# SCH-mfd-menu-panel.net
KiCad netlist of a schematic drawn in EasyEDA
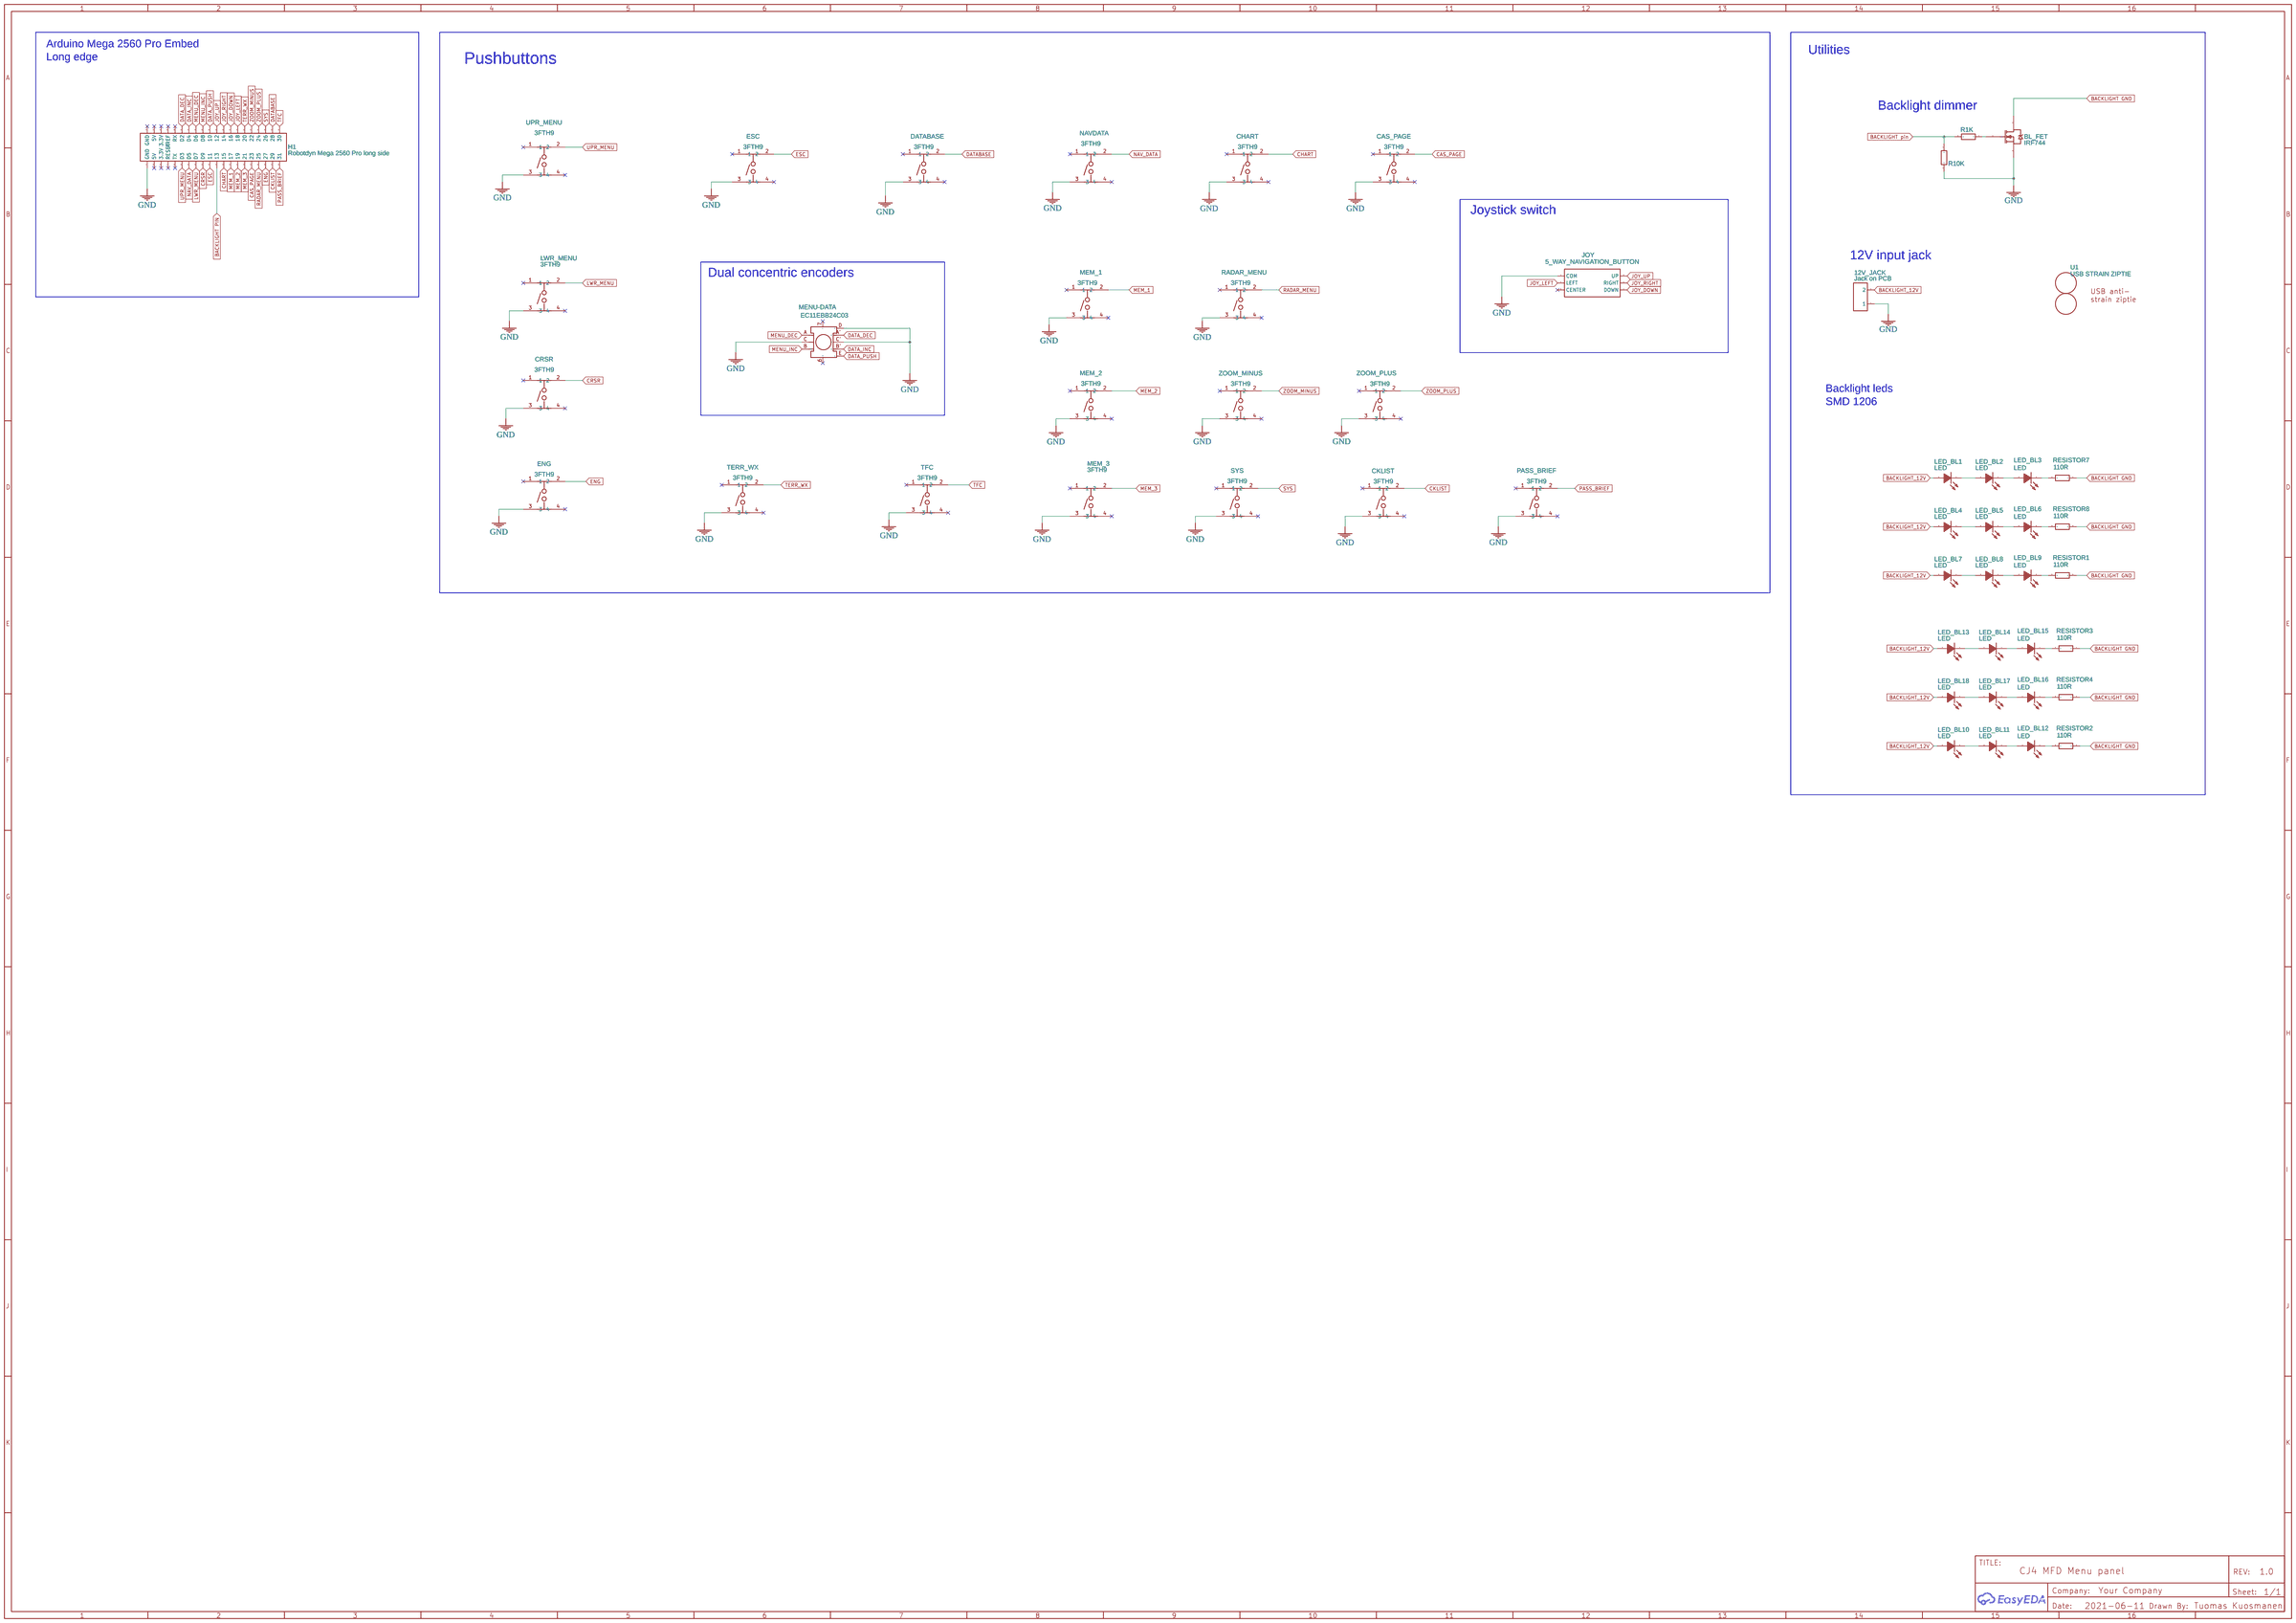
[diagram p0: schematic sheet]

(export (version "E")
  (design (tool "Eeschema 10.0.6"))
  (components
    (comp (ref "12V_JACK") (value "Jack on PCB") (libsource (lib "") (part "J-Header-Male-2.54_1x2")))
    (comp (ref "BL_FET") (value "IRF744") (libsource (lib "") (part "IRF744")))
    (comp (ref "CAS_PAGE")
      (value "3FTH9")
      (fields (field (name "BOM_Supplier Part") "679-3730-5-ND"))
      (libsource (lib "") (part "3FTH9_13"))
    )
    (comp (ref "CHART")
      (value "3FTH9")
      (fields (field (name "BOM_Supplier Part") "679-3730-5-ND"))
      (libsource (lib "") (part "3FTH9_6"))
    )
    (comp (ref "CKLIST")
      (value "3FTH9")
      (fields (field (name "BOM_Supplier Part") "679-3730-5-ND"))
      (libsource (lib "") (part "3FTH9_7"))
    )
    (comp (ref "CRSR")
      (value "3FTH9")
      (fields (field (name "BOM_Supplier Part") "679-3730-5-ND"))
      (libsource (lib "") (part "3FTH9_12"))
    )
    (comp (ref "DATABASE")
      (value "3FTH9")
      (fields (field (name "BOM_Supplier Part") "679-3730-5-ND"))
      (libsource (lib "") (part "3FTH9_4"))
    )
    (comp (ref "ENG")
      (value "3FTH9")
      (fields (field (name "BOM_Supplier Part") "679-3730-5-ND"))
      (libsource (lib "") (part "3FTH9_2"))
    )
    (comp (ref "ESC")
      (value "3FTH9")
      (fields (field (name "BOM_Supplier Part") "679-3730-5-ND"))
      (libsource (lib "") (part "3FTH9_16"))
    )
    (comp (ref "H1")
      (value "Robotdyn Mega 2560 Pro long side")
      (fields
        (field (name "BOM_Manufacturer Part") "Header-Male-2.54_2x20")
        (field (name "BOM_Supplier Part") "C50980")
      )
      (libsource (lib "") (part "Header-Male-2.54_2x20"))
    )
    (comp (ref "JOY")
      (value "5_WAY_NAVIGATION_BUTTON")
      (fields (field (name "BOM_Manufacturer Part") "New SchematicLib"))
      (libsource (lib "") (part "5_WAY_NAVIGATION_BUTTON"))
    )
    (comp (ref "LED_BL1")
      (value "LED")
      (fields
        (field (name "BOM_Manufacturer Part") "HQ17-2102UYOC")
        (field (name "BOM_Supplier Part") "C154481")
      )
      (libsource (lib "") (part "HQ17-2102UYOC"))
    )
    (comp (ref "LED_BL2")
      (value "LED")
      (fields
        (field (name "BOM_Manufacturer Part") "HQ17-2102UYOC")
        (field (name "BOM_Supplier Part") "C154481")
      )
      (libsource (lib "") (part "HQ17-2102UYOC"))
    )
    (comp (ref "LED_BL3")
      (value "LED")
      (fields
        (field (name "BOM_Manufacturer Part") "HQ17-2102UYOC")
        (field (name "BOM_Supplier Part") "C154481")
      )
      (libsource (lib "") (part "HQ17-2102UYOC"))
    )
    (comp (ref "LED_BL4")
      (value "LED")
      (fields
        (field (name "BOM_Manufacturer Part") "HQ17-2102UYOC")
        (field (name "BOM_Supplier Part") "C154481")
      )
      (libsource (lib "") (part "HQ17-2102UYOC"))
    )
    (comp (ref "LED_BL5")
      (value "LED")
      (fields
        (field (name "BOM_Manufacturer Part") "HQ17-2102UYOC")
        (field (name "BOM_Supplier Part") "C154481")
      )
      (libsource (lib "") (part "HQ17-2102UYOC"))
    )
    (comp (ref "LED_BL6")
      (value "LED")
      (fields
        (field (name "BOM_Manufacturer Part") "HQ17-2102UYOC")
        (field (name "BOM_Supplier Part") "C154481")
      )
      (libsource (lib "") (part "HQ17-2102UYOC"))
    )
    (comp (ref "LED_BL7")
      (value "LED")
      (fields
        (field (name "BOM_Manufacturer Part") "HQ17-2102UYOC")
        (field (name "BOM_Supplier Part") "C154481")
      )
      (libsource (lib "") (part "HQ17-2102UYOC"))
    )
    (comp (ref "LED_BL8")
      (value "LED")
      (fields
        (field (name "BOM_Manufacturer Part") "HQ17-2102UYOC")
        (field (name "BOM_Supplier Part") "C154481")
      )
      (libsource (lib "") (part "HQ17-2102UYOC"))
    )
    (comp (ref "LED_BL9")
      (value "LED")
      (fields
        (field (name "BOM_Manufacturer Part") "HQ17-2102UYOC")
        (field (name "BOM_Supplier Part") "C154481")
      )
      (libsource (lib "") (part "HQ17-2102UYOC"))
    )
    (comp (ref "LED_BL10")
      (value "LED")
      (fields
        (field (name "BOM_Manufacturer Part") "HQ17-2102UYOC")
        (field (name "BOM_Supplier Part") "C154481")
      )
      (libsource (lib "") (part "HQ17-2102UYOC"))
    )
    (comp (ref "LED_BL11")
      (value "LED")
      (fields
        (field (name "BOM_Manufacturer Part") "HQ17-2102UYOC")
        (field (name "BOM_Supplier Part") "C154481")
      )
      (libsource (lib "") (part "HQ17-2102UYOC"))
    )
    (comp (ref "LED_BL12")
      (value "LED")
      (fields
        (field (name "BOM_Manufacturer Part") "HQ17-2102UYOC")
        (field (name "BOM_Supplier Part") "C154481")
      )
      (libsource (lib "") (part "HQ17-2102UYOC"))
    )
    (comp (ref "LED_BL13")
      (value "LED")
      (fields
        (field (name "BOM_Manufacturer Part") "HQ17-2102UYOC")
        (field (name "BOM_Supplier Part") "C154481")
      )
      (libsource (lib "") (part "HQ17-2102UYOC"))
    )
    (comp (ref "LED_BL14")
      (value "LED")
      (fields
        (field (name "BOM_Manufacturer Part") "HQ17-2102UYOC")
        (field (name "BOM_Supplier Part") "C154481")
      )
      (libsource (lib "") (part "HQ17-2102UYOC"))
    )
    (comp (ref "LED_BL15")
      (value "LED")
      (fields
        (field (name "BOM_Manufacturer Part") "HQ17-2102UYOC")
        (field (name "BOM_Supplier Part") "C154481")
      )
      (libsource (lib "") (part "HQ17-2102UYOC"))
    )
    (comp (ref "LED_BL16")
      (value "LED")
      (fields
        (field (name "BOM_Manufacturer Part") "HQ17-2102UYOC")
        (field (name "BOM_Supplier Part") "C154481")
      )
      (libsource (lib "") (part "HQ17-2102UYOC"))
    )
    (comp (ref "LED_BL17")
      (value "LED")
      (fields
        (field (name "BOM_Manufacturer Part") "HQ17-2102UYOC")
        (field (name "BOM_Supplier Part") "C154481")
      )
      (libsource (lib "") (part "HQ17-2102UYOC"))
    )
    (comp (ref "LED_BL18")
      (value "LED")
      (fields
        (field (name "BOM_Manufacturer Part") "HQ17-2102UYOC")
        (field (name "BOM_Supplier Part") "C154481")
      )
      (libsource (lib "") (part "HQ17-2102UYOC"))
    )
    (comp (ref "LWR_MENU")
      (value "3FTH9")
      (fields (field (name "BOM_Supplier Part") "679-3730-5-ND"))
      (libsource (lib "") (part "3FTH9_1"))
    )
    (comp (ref "MEM_1")
      (value "3FTH9")
      (fields (field (name "BOM_Supplier Part") "679-3730-5-ND"))
      (libsource (lib "") (part "3FTH9"))
    )
    (comp (ref "MEM_2")
      (value "3FTH9")
      (fields (field (name "BOM_Supplier Part") "679-3730-5-ND"))
      (libsource (lib "") (part "3FTH9"))
    )
    (comp (ref "MEM_3")
      (value "3FTH9")
      (fields (field (name "BOM_Supplier Part") "679-3730-5-ND"))
      (libsource (lib "") (part "3FTH9"))
    )
    (comp (ref "MENU-DATA")
      (value "EC11EBB24C03")
      (fields (field (name "BOM_Supplier Part") "C470790"))
      (libsource (lib "") (part "EC11EBB24C03"))
    )
    (comp (ref "NAVDATA")
      (value "3FTH9")
      (fields (field (name "BOM_Supplier Part") "679-3730-5-ND"))
      (libsource (lib "") (part "3FTH9_15"))
    )
    (comp (ref "PASS_BRIEF")
      (value "3FTH9")
      (fields (field (name "BOM_Supplier Part") "679-3730-5-ND"))
      (libsource (lib "") (part "3FTH9_5"))
    )
    (comp (ref "PROTECT_BL1")
      (value "R1K")
      (fields
        (field (name "BOM_Manufacturer Part") "1206W4J0331T5E")
        (field (name "BOM_Supplier Part") "C25374")
      )
      (libsource (lib "") (part "1206W4J0331T5E_1"))
    )
    (comp (ref "RADAR_MENU")
      (value "3FTH9")
      (fields (field (name "BOM_Supplier Part") "679-3730-5-ND"))
      (libsource (lib "") (part "3FTH9_3"))
    )
    (comp (ref "RESISTOR1")
      (value "110R")
      (fields
        (field (name "BOM_Manufacturer Part") "1206W4J0331T5E")
        (field (name "BOM_Supplier Part") "C25374")
      )
      (libsource (lib "") (part "1206W4J0331T5E"))
    )
    (comp (ref "RESISTOR2")
      (value "110R")
      (fields
        (field (name "BOM_Manufacturer Part") "1206W4J0331T5E")
        (field (name "BOM_Supplier Part") "C25374")
      )
      (libsource (lib "") (part "1206W4J0331T5E"))
    )
    (comp (ref "RESISTOR3")
      (value "110R")
      (fields
        (field (name "BOM_Manufacturer Part") "1206W4J0331T5E")
        (field (name "BOM_Supplier Part") "C25374")
      )
      (libsource (lib "") (part "1206W4J0331T5E"))
    )
    (comp (ref "RESISTOR4")
      (value "110R")
      (fields
        (field (name "BOM_Manufacturer Part") "1206W4J0331T5E")
        (field (name "BOM_Supplier Part") "C25374")
      )
      (libsource (lib "") (part "1206W4J0331T5E"))
    )
    (comp (ref "RESISTOR7")
      (value "110R")
      (fields
        (field (name "BOM_Manufacturer Part") "1206W4J0331T5E")
        (field (name "BOM_Supplier Part") "C25374")
      )
      (libsource (lib "") (part "1206W4J0331T5E"))
    )
    (comp (ref "RESISTOR8")
      (value "110R")
      (fields
        (field (name "BOM_Manufacturer Part") "1206W4J0331T5E")
        (field (name "BOM_Supplier Part") "C25374")
      )
      (libsource (lib "") (part "1206W4J0331T5E"))
    )
    (comp (ref "R_ANN5")
      (value "R10K")
      (fields
        (field (name "BOM_Manufacturer Part") "1206W4J0331T5E")
        (field (name "BOM_Supplier Part") "C25374")
      )
      (libsource (lib "") (part "1206W4J0331T5E_2"))
    )
    (comp (ref "SYS")
      (value "3FTH9")
      (fields (field (name "BOM_Supplier Part") "679-3730-5-ND"))
      (libsource (lib "") (part "3FTH9_14"))
    )
    (comp (ref "TERR_WX")
      (value "3FTH9")
      (fields (field (name "BOM_Supplier Part") "679-3730-5-ND"))
      (libsource (lib "") (part "3FTH9_17"))
    )
    (comp (ref "TFC")
      (value "3FTH9")
      (fields (field (name "BOM_Supplier Part") "679-3730-5-ND"))
      (libsource (lib "") (part "3FTH9_8"))
    )
    (comp (ref "U1") (value "USB STRAIN ZIPTIE") (libsource (lib "") (part "USB STRAIN ZIPTIE")))
    (comp (ref "UPR_MENU")
      (value "3FTH9")
      (fields (field (name "BOM_Supplier Part") "679-3730-5-ND"))
      (libsource (lib "") (part "3FTH9_11"))
    )
    (comp (ref "ZOOM_MINUS")
      (value "3FTH9")
      (fields (field (name "BOM_Supplier Part") "679-3730-5-ND"))
      (libsource (lib "") (part "3FTH9_10"))
    )
    (comp (ref "ZOOM_PLUS")
      (value "3FTH9")
      (fields (field (name "BOM_Supplier Part") "679-3730-5-ND"))
      (libsource (lib "") (part "3FTH9_9"))
    )
  )
  (nets
    (net (code "1") (name "BACKLIGHT GND") (class "Default")
      (node (ref "BL_FET") (pin "2") (pinfunction "D_2") (pintype "unspecified"))
      (node (ref "RESISTOR1") (pin "1") (pinfunction "1_1") (pintype "input"))
      (node (ref "RESISTOR2") (pin "1") (pinfunction "1_1") (pintype "input"))
      (node (ref "RESISTOR3") (pin "1") (pinfunction "1_1") (pintype "input"))
      (node (ref "RESISTOR4") (pin "1") (pinfunction "1_1") (pintype "input"))
      (node (ref "RESISTOR7") (pin "1") (pinfunction "1_1") (pintype "input"))
      (node (ref "RESISTOR8") (pin "1") (pinfunction "1_1") (pintype "input"))
    )
    (net (code "2") (name "BACKLIGHT PIN") (class "Default")
      (node (ref "H1") (pin "21") (pinfunction "13_21") (pintype "input"))
    )
    (net (code "3") (name "BACKLIGHT pin") (class "Default")
      (node (ref "PROTECT_BL1") (pin "2") (pinfunction "2_2") (pintype "input"))
      (node (ref "R_ANN5") (pin "1") (pinfunction "1_1") (pintype "input"))
    )
    (net (code "4") (name "BACKLIGHT_12V") (class "Default")
      (node (ref "12V_JACK") (pin "2") (pinfunction "2_2") (pintype "unspecified"))
      (node (ref "LED_BL1") (pin "2") (pinfunction "A_2") (pintype "unspecified"))
      (node (ref "LED_BL10") (pin "2") (pinfunction "A_2") (pintype "unspecified"))
      (node (ref "LED_BL13") (pin "2") (pinfunction "A_2") (pintype "unspecified"))
      (node (ref "LED_BL18") (pin "2") (pinfunction "A_2") (pintype "unspecified"))
      (node (ref "LED_BL4") (pin "2") (pinfunction "A_2") (pintype "unspecified"))
      (node (ref "LED_BL7") (pin "2") (pinfunction "A_2") (pintype "unspecified"))
    )
    (net (code "5") (name "CAS_PAGE") (class "Default")
      (node (ref "CAS_PAGE") (pin "2") (pinfunction "2_2") (pintype "unspecified"))
      (node (ref "H1") (pin "31") (pinfunction "23_31") (pintype "input"))
    )
    (net (code "6") (name "CHART") (class "Default")
      (node (ref "CHART") (pin "2") (pinfunction "2_2") (pintype "unspecified"))
      (node (ref "H1") (pin "23") (pinfunction "15_23") (pintype "input"))
    )
    (net (code "7") (name "CKLIST") (class "Default")
      (node (ref "CKLIST") (pin "2") (pinfunction "2_2") (pintype "unspecified"))
      (node (ref "H1") (pin "37") (pinfunction "29_37") (pintype "input"))
    )
    (net (code "8") (name "CRSR") (class "Default")
      (node (ref "CRSR") (pin "2") (pinfunction "2_2") (pintype "unspecified"))
      (node (ref "H1") (pin "17") (pinfunction "D9_17") (pintype "input"))
    )
    (net (code "9") (name "DATABASE") (class "Default")
      (node (ref "DATABASE") (pin "2") (pinfunction "2_2") (pintype "unspecified"))
      (node (ref "H1") (pin "38") (pinfunction "28_38") (pintype "input"))
    )
    (net (code "10") (name "DATA_DEC") (class "Default")
      (node (ref "H1") (pin "12") (pinfunction "D2_12") (pintype "input"))
      (node (ref "MENU-DATA") (pin "A'") (pinfunction "A'_A'") (pintype "unspecified"))
    )
    (net (code "11") (name "DATA_INC") (class "Default")
      (node (ref "H1") (pin "14") (pinfunction "D4_14") (pintype "input"))
      (node (ref "MENU-DATA") (pin "B'") (pinfunction "B'_B'") (pintype "unspecified"))
    )
    (net (code "12") (name "DATA_PUSH") (class "Default")
      (node (ref "H1") (pin "20") (pinfunction "10_20") (pintype "input"))
      (node (ref "MENU-DATA") (pin "E") (pinfunction "E_E") (pintype "unspecified"))
    )
    (net (code "13") (name "ENG") (class "Default")
      (node (ref "ENG") (pin "2") (pinfunction "2_2") (pintype "unspecified"))
      (node (ref "H1") (pin "35") (pinfunction "27_35") (pintype "input"))
    )
    (net (code "14") (name "ESC") (class "Default")
      (node (ref "ESC") (pin "2") (pinfunction "2_2") (pintype "unspecified"))
      (node (ref "H1") (pin "19") (pinfunction "11_19") (pintype "input"))
    )
    (net (code "15") (name "GND") (class "Default")
      (node (ref "12V_JACK") (pin "1") (pinfunction "1_1") (pintype "unspecified"))
      (node (ref "BL_FET") (pin "3") (pinfunction "S_3") (pintype "unspecified"))
      (node (ref "CAS_PAGE") (pin "3") (pinfunction "3_3") (pintype "unspecified"))
      (node (ref "CHART") (pin "3") (pinfunction "3_3") (pintype "unspecified"))
      (node (ref "CKLIST") (pin "3") (pinfunction "3_3") (pintype "unspecified"))
      (node (ref "CRSR") (pin "3") (pinfunction "3_3") (pintype "unspecified"))
      (node (ref "DATABASE") (pin "3") (pinfunction "3_3") (pintype "unspecified"))
      (node (ref "ENG") (pin "3") (pinfunction "3_3") (pintype "unspecified"))
      (node (ref "ESC") (pin "3") (pinfunction "3_3") (pintype "unspecified"))
      (node (ref "H1") (pin "1") (pinfunction "GND_1") (pintype "input"))
      (node (ref "JOY") (pin "1") (pinfunction "COM_1") (pintype "unspecified"))
      (node (ref "LWR_MENU") (pin "3") (pinfunction "3_3") (pintype "unspecified"))
      (node (ref "MEM_1") (pin "3") (pinfunction "3_3") (pintype "unspecified"))
      (node (ref "MEM_2") (pin "3") (pinfunction "3_3") (pintype "unspecified"))
      (node (ref "MEM_3") (pin "3") (pinfunction "3_3") (pintype "unspecified"))
      (node (ref "MENU-DATA") (pin "C") (pinfunction "C_C") (pintype "unspecified"))
      (node (ref "MENU-DATA") (pin "C'") (pinfunction "C'_C'") (pintype "unspecified"))
      (node (ref "MENU-DATA") (pin "D") (pinfunction "D_D") (pintype "unspecified"))
      (node (ref "NAVDATA") (pin "3") (pinfunction "3_3") (pintype "unspecified"))
      (node (ref "PASS_BRIEF") (pin "3") (pinfunction "3_3") (pintype "unspecified"))
      (node (ref "RADAR_MENU") (pin "3") (pinfunction "3_3") (pintype "unspecified"))
      (node (ref "R_ANN5") (pin "2") (pinfunction "2_2") (pintype "input"))
      (node (ref "SYS") (pin "3") (pinfunction "3_3") (pintype "unspecified"))
      (node (ref "TERR_WX") (pin "3") (pinfunction "3_3") (pintype "unspecified"))
      (node (ref "TFC") (pin "3") (pinfunction "3_3") (pintype "unspecified"))
      (node (ref "UPR_MENU") (pin "3") (pinfunction "3_3") (pintype "unspecified"))
      (node (ref "ZOOM_MINUS") (pin "3") (pinfunction "3_3") (pintype "unspecified"))
      (node (ref "ZOOM_PLUS") (pin "3") (pinfunction "3_3") (pintype "unspecified"))
    )
    (net (code "16") (name "JOY_DOWN") (class "Default")
      (node (ref "H1") (pin "26") (pinfunction "16_26") (pintype "input"))
      (node (ref "JOY") (pin "4") (pinfunction "DOWN_4") (pintype "unspecified"))
    )
    (net (code "17") (name "JOY_LEFT") (class "Default")
      (node (ref "H1") (pin "28") (pinfunction "18_28") (pintype "input"))
      (node (ref "JOY") (pin "2") (pinfunction "LEFT_2") (pintype "unspecified"))
    )
    (net (code "18") (name "JOY_RIGHT") (class "Default")
      (node (ref "H1") (pin "24") (pinfunction "14_24") (pintype "input"))
      (node (ref "JOY") (pin "5") (pinfunction "RIGHT_5") (pintype "unspecified"))
    )
    (net (code "19") (name "JOY_UP") (class "Default")
      (node (ref "H1") (pin "22") (pinfunction "12_22") (pintype "input"))
      (node (ref "JOY") (pin "6") (pinfunction "UP_6") (pintype "unspecified"))
    )
    (net (code "20") (name "LWR_MENU") (class "Default")
      (node (ref "H1") (pin "15") (pinfunction "D7_15") (pintype "input"))
      (node (ref "LWR_MENU") (pin "2") (pinfunction "2_2") (pintype "unspecified"))
    )
    (net (code "21") (name "MEM_1") (class "Default")
      (node (ref "H1") (pin "25") (pinfunction "17_25") (pintype "input"))
      (node (ref "MEM_1") (pin "2") (pinfunction "2_2") (pintype "unspecified"))
    )
    (net (code "22") (name "MEM_2") (class "Default")
      (node (ref "H1") (pin "27") (pinfunction "19_27") (pintype "input"))
      (node (ref "MEM_2") (pin "2") (pinfunction "2_2") (pintype "unspecified"))
    )
    (net (code "23") (name "MEM_3") (class "Default")
      (node (ref "H1") (pin "29") (pinfunction "21_29") (pintype "input"))
      (node (ref "MEM_3") (pin "2") (pinfunction "2_2") (pintype "unspecified"))
    )
    (net (code "24") (name "MENU_DEC") (class "Default")
      (node (ref "H1") (pin "16") (pinfunction "D6_16") (pintype "input"))
      (node (ref "MENU-DATA") (pin "A") (pinfunction "A_A") (pintype "unspecified"))
    )
    (net (code "25") (name "MENU_INC") (class "Default")
      (node (ref "H1") (pin "18") (pinfunction "D8_18") (pintype "input"))
      (node (ref "MENU-DATA") (pin "B") (pinfunction "B_B") (pintype "unspecified"))
    )
    (net (code "26") (name "NAV_DATA") (class "Default")
      (node (ref "H1") (pin "13") (pinfunction "D5_13") (pintype "input"))
      (node (ref "NAVDATA") (pin "2") (pinfunction "2_2") (pintype "unspecified"))
    )
    (net (code "27") (name "Net-(BL_FET-G)") (class "Default")
      (node (ref "BL_FET") (pin "1") (pinfunction "G_1") (pintype "unspecified"))
      (node (ref "PROTECT_BL1") (pin "1") (pinfunction "1_1") (pintype "input"))
    )
    (net (code "28") (name "Net-(LED_BL1-K)") (class "Default")
      (node (ref "LED_BL1") (pin "1") (pinfunction "K_1") (pintype "unspecified"))
      (node (ref "LED_BL2") (pin "2") (pinfunction "A_2") (pintype "unspecified"))
    )
    (net (code "29") (name "Net-(LED_BL2-K)") (class "Default")
      (node (ref "LED_BL2") (pin "1") (pinfunction "K_1") (pintype "unspecified"))
      (node (ref "LED_BL3") (pin "2") (pinfunction "A_2") (pintype "unspecified"))
    )
    (net (code "30") (name "Net-(LED_BL3-K)") (class "Default")
      (node (ref "LED_BL3") (pin "1") (pinfunction "K_1") (pintype "unspecified"))
      (node (ref "RESISTOR7") (pin "2") (pinfunction "2_2") (pintype "input"))
    )
    (net (code "31") (name "Net-(LED_BL4-K)") (class "Default")
      (node (ref "LED_BL4") (pin "1") (pinfunction "K_1") (pintype "unspecified"))
      (node (ref "LED_BL5") (pin "2") (pinfunction "A_2") (pintype "unspecified"))
    )
    (net (code "32") (name "Net-(LED_BL5-K)") (class "Default")
      (node (ref "LED_BL5") (pin "1") (pinfunction "K_1") (pintype "unspecified"))
      (node (ref "LED_BL6") (pin "2") (pinfunction "A_2") (pintype "unspecified"))
    )
    (net (code "33") (name "Net-(LED_BL6-K)") (class "Default")
      (node (ref "LED_BL6") (pin "1") (pinfunction "K_1") (pintype "unspecified"))
      (node (ref "RESISTOR8") (pin "2") (pinfunction "2_2") (pintype "input"))
    )
    (net (code "34") (name "Net-(LED_BL7-K)") (class "Default")
      (node (ref "LED_BL7") (pin "1") (pinfunction "K_1") (pintype "unspecified"))
      (node (ref "LED_BL8") (pin "2") (pinfunction "A_2") (pintype "unspecified"))
    )
    (net (code "35") (name "Net-(LED_BL8-K)") (class "Default")
      (node (ref "LED_BL8") (pin "1") (pinfunction "K_1") (pintype "unspecified"))
      (node (ref "LED_BL9") (pin "2") (pinfunction "A_2") (pintype "unspecified"))
    )
    (net (code "36") (name "Net-(LED_BL9-K)") (class "Default")
      (node (ref "LED_BL9") (pin "1") (pinfunction "K_1") (pintype "unspecified"))
      (node (ref "RESISTOR1") (pin "2") (pinfunction "2_2") (pintype "input"))
    )
    (net (code "37") (name "Net-(LED_BL10-K)") (class "Default")
      (node (ref "LED_BL10") (pin "1") (pinfunction "K_1") (pintype "unspecified"))
      (node (ref "LED_BL11") (pin "2") (pinfunction "A_2") (pintype "unspecified"))
    )
    (net (code "38") (name "Net-(LED_BL11-K)") (class "Default")
      (node (ref "LED_BL11") (pin "1") (pinfunction "K_1") (pintype "unspecified"))
      (node (ref "LED_BL12") (pin "2") (pinfunction "A_2") (pintype "unspecified"))
    )
    (net (code "39") (name "Net-(LED_BL12-K)") (class "Default")
      (node (ref "LED_BL12") (pin "1") (pinfunction "K_1") (pintype "unspecified"))
      (node (ref "RESISTOR2") (pin "2") (pinfunction "2_2") (pintype "input"))
    )
    (net (code "40") (name "Net-(LED_BL13-K)") (class "Default")
      (node (ref "LED_BL13") (pin "1") (pinfunction "K_1") (pintype "unspecified"))
      (node (ref "LED_BL14") (pin "2") (pinfunction "A_2") (pintype "unspecified"))
    )
    (net (code "41") (name "Net-(LED_BL14-K)") (class "Default")
      (node (ref "LED_BL14") (pin "1") (pinfunction "K_1") (pintype "unspecified"))
      (node (ref "LED_BL15") (pin "2") (pinfunction "A_2") (pintype "unspecified"))
    )
    (net (code "42") (name "Net-(LED_BL15-K)") (class "Default")
      (node (ref "LED_BL15") (pin "1") (pinfunction "K_1") (pintype "unspecified"))
      (node (ref "RESISTOR3") (pin "2") (pinfunction "2_2") (pintype "input"))
    )
    (net (code "43") (name "Net-(LED_BL16-A)") (class "Default")
      (node (ref "LED_BL16") (pin "2") (pinfunction "A_2") (pintype "unspecified"))
      (node (ref "LED_BL17") (pin "1") (pinfunction "K_1") (pintype "unspecified"))
    )
    (net (code "44") (name "Net-(LED_BL16-K)") (class "Default")
      (node (ref "LED_BL16") (pin "1") (pinfunction "K_1") (pintype "unspecified"))
      (node (ref "RESISTOR4") (pin "2") (pinfunction "2_2") (pintype "input"))
    )
    (net (code "45") (name "Net-(LED_BL17-A)") (class "Default")
      (node (ref "LED_BL17") (pin "2") (pinfunction "A_2") (pintype "unspecified"))
      (node (ref "LED_BL18") (pin "1") (pinfunction "K_1") (pintype "unspecified"))
    )
    (net (code "46") (name "PASS_BRIEF") (class "Default")
      (node (ref "H1") (pin "39") (pinfunction "31_39") (pintype "input"))
      (node (ref "PASS_BRIEF") (pin "2") (pinfunction "2_2") (pintype "unspecified"))
    )
    (net (code "47") (name "RADAR_MENU") (class "Default")
      (node (ref "H1") (pin "33") (pinfunction "25_33") (pintype "input"))
      (node (ref "RADAR_MENU") (pin "2") (pinfunction "2_2") (pintype "unspecified"))
    )
    (net (code "48") (name "SYS") (class "Default")
      (node (ref "H1") (pin "36") (pinfunction "26_36") (pintype "input"))
      (node (ref "SYS") (pin "2") (pinfunction "2_2") (pintype "unspecified"))
    )
    (net (code "49") (name "TERR_WX") (class "Default")
      (node (ref "H1") (pin "30") (pinfunction "20_30") (pintype "input"))
      (node (ref "TERR_WX") (pin "2") (pinfunction "2_2") (pintype "unspecified"))
    )
    (net (code "50") (name "TFC") (class "Default")
      (node (ref "H1") (pin "40") (pinfunction "30_40") (pintype "input"))
      (node (ref "TFC") (pin "2") (pinfunction "2_2") (pintype "unspecified"))
    )
    (net (code "51") (name "UPR_MENU") (class "Default")
      (node (ref "H1") (pin "11") (pinfunction "D3_11") (pintype "input"))
      (node (ref "UPR_MENU") (pin "2") (pinfunction "2_2") (pintype "unspecified"))
    )
    (net (code "52") (name "ZOOM_MINUS") (class "Default")
      (node (ref "H1") (pin "32") (pinfunction "22_32") (pintype "input"))
      (node (ref "ZOOM_MINUS") (pin "2") (pinfunction "2_2") (pintype "unspecified"))
    )
    (net (code "53") (name "ZOOM_PLUS") (class "Default")
      (node (ref "H1") (pin "34") (pinfunction "24_34") (pintype "input"))
      (node (ref "ZOOM_PLUS") (pin "2") (pinfunction "2_2") (pintype "unspecified"))
    )
    (net (code "54") (name "unconnected-(CAS_PAGE-Pad1)") (class "Default")
      (node (ref "CAS_PAGE") (pin "1") (pinfunction "1_1") (pintype "unspecified+no_connect"))
    )
    (net (code "55") (name "unconnected-(CAS_PAGE-Pad4)") (class "Default")
      (node (ref "CAS_PAGE") (pin "4") (pinfunction "4_4") (pintype "unspecified+no_connect"))
    )
    (net (code "56") (name "unconnected-(CHART-Pad1)") (class "Default")
      (node (ref "CHART") (pin "1") (pinfunction "1_1") (pintype "unspecified+no_connect"))
    )
    (net (code "57") (name "unconnected-(CHART-Pad4)") (class "Default")
      (node (ref "CHART") (pin "4") (pinfunction "4_4") (pintype "unspecified+no_connect"))
    )
    (net (code "58") (name "unconnected-(CKLIST-Pad1)") (class "Default")
      (node (ref "CKLIST") (pin "1") (pinfunction "1_1") (pintype "unspecified+no_connect"))
    )
    (net (code "59") (name "unconnected-(CKLIST-Pad4)") (class "Default")
      (node (ref "CKLIST") (pin "4") (pinfunction "4_4") (pintype "unspecified+no_connect"))
    )
    (net (code "60") (name "unconnected-(CRSR-Pad1)") (class "Default")
      (node (ref "CRSR") (pin "1") (pinfunction "1_1") (pintype "unspecified+no_connect"))
    )
    (net (code "61") (name "unconnected-(CRSR-Pad4)") (class "Default")
      (node (ref "CRSR") (pin "4") (pinfunction "4_4") (pintype "unspecified+no_connect"))
    )
    (net (code "62") (name "unconnected-(DATABASE-Pad1)") (class "Default")
      (node (ref "DATABASE") (pin "1") (pinfunction "1_1") (pintype "unspecified+no_connect"))
    )
    (net (code "63") (name "unconnected-(DATABASE-Pad4)") (class "Default")
      (node (ref "DATABASE") (pin "4") (pinfunction "4_4") (pintype "unspecified+no_connect"))
    )
    (net (code "64") (name "unconnected-(ENG-Pad1)") (class "Default")
      (node (ref "ENG") (pin "1") (pinfunction "1_1") (pintype "unspecified+no_connect"))
    )
    (net (code "65") (name "unconnected-(ENG-Pad4)") (class "Default")
      (node (ref "ENG") (pin "4") (pinfunction "4_4") (pintype "unspecified+no_connect"))
    )
    (net (code "66") (name "unconnected-(ESC-Pad1)") (class "Default")
      (node (ref "ESC") (pin "1") (pinfunction "1_1") (pintype "unspecified+no_connect"))
    )
    (net (code "67") (name "unconnected-(ESC-Pad4)") (class "Default")
      (node (ref "ESC") (pin "4") (pinfunction "4_4") (pintype "unspecified+no_connect"))
    )
    (net (code "68") (name "unconnected-(H1-3.3V-Pad5)") (class "Default")
      (node (ref "H1") (pin "5") (pinfunction "3.3V_5") (pintype "input+no_connect"))
    )
    (net (code "69") (name "unconnected-(H1-3.3V-Pad6)") (class "Default")
      (node (ref "H1") (pin "6") (pinfunction "3.3V_6") (pintype "input+no_connect"))
    )
    (net (code "70") (name "unconnected-(H1-5V-Pad3)") (class "Default")
      (node (ref "H1") (pin "3") (pinfunction "5V_3") (pintype "input+no_connect"))
    )
    (net (code "71") (name "unconnected-(H1-5V-Pad4)") (class "Default")
      (node (ref "H1") (pin "4") (pinfunction "5V_4") (pintype "input+no_connect"))
    )
    (net (code "72") (name "unconnected-(H1-AREF-Pad8)") (class "Default")
      (node (ref "H1") (pin "8") (pinfunction "AREF_8") (pintype "input+no_connect"))
    )
    (net (code "73") (name "unconnected-(H1-GND-Pad2)") (class "Default")
      (node (ref "H1") (pin "2") (pinfunction "GND_2") (pintype "input+no_connect"))
    )
    (net (code "74") (name "unconnected-(H1-RESET-Pad7)") (class "Default")
      (node (ref "H1") (pin "7") (pinfunction "RESET_7") (pintype "input+no_connect"))
    )
    (net (code "75") (name "unconnected-(H1-RX-Pad10)") (class "Default")
      (node (ref "H1") (pin "10") (pinfunction "RX_10") (pintype "input+no_connect"))
    )
    (net (code "76") (name "unconnected-(H1-TX-Pad9)") (class "Default")
      (node (ref "H1") (pin "9") (pinfunction "TX_9") (pintype "input+no_connect"))
    )
    (net (code "77") (name "unconnected-(JOY-CENTER-Pad3)") (class "Default")
      (node (ref "JOY") (pin "3") (pinfunction "CENTER_3") (pintype "unspecified+no_connect"))
    )
    (net (code "78") (name "unconnected-(LWR_MENU-Pad1)") (class "Default")
      (node (ref "LWR_MENU") (pin "1") (pinfunction "1_1") (pintype "unspecified+no_connect"))
    )
    (net (code "79") (name "unconnected-(LWR_MENU-Pad4)") (class "Default")
      (node (ref "LWR_MENU") (pin "4") (pinfunction "4_4") (pintype "unspecified+no_connect"))
    )
    (net (code "80") (name "unconnected-(MEM_1-Pad1)") (class "Default")
      (node (ref "MEM_1") (pin "1") (pinfunction "1_1") (pintype "unspecified+no_connect"))
    )
    (net (code "81") (name "unconnected-(MEM_1-Pad4)") (class "Default")
      (node (ref "MEM_1") (pin "4") (pinfunction "4_4") (pintype "unspecified+no_connect"))
    )
    (net (code "82") (name "unconnected-(MEM_2-Pad1)") (class "Default")
      (node (ref "MEM_2") (pin "1") (pinfunction "1_1") (pintype "unspecified+no_connect"))
    )
    (net (code "83") (name "unconnected-(MEM_2-Pad4)") (class "Default")
      (node (ref "MEM_2") (pin "4") (pinfunction "4_4") (pintype "unspecified+no_connect"))
    )
    (net (code "84") (name "unconnected-(MEM_3-Pad1)") (class "Default")
      (node (ref "MEM_3") (pin "1") (pinfunction "1_1") (pintype "unspecified+no_connect"))
    )
    (net (code "85") (name "unconnected-(MEM_3-Pad4)") (class "Default")
      (node (ref "MEM_3") (pin "4") (pinfunction "4_4") (pintype "unspecified+no_connect"))
    )
    (net (code "86") (name "unconnected-(MENU-DATA-Pad6)") (class "Default")
      (node (ref "MENU-DATA") (pin "6") (pinfunction "6_6") (pintype "unspecified+no_connect"))
    )
    (net (code "87") (name "unconnected-(MENU-DATA-Pad7)") (class "Default")
      (node (ref "MENU-DATA") (pin "7") (pinfunction "7_7") (pintype "unspecified+no_connect"))
    )
    (net (code "88") (name "unconnected-(NAVDATA-Pad1)") (class "Default")
      (node (ref "NAVDATA") (pin "1") (pinfunction "1_1") (pintype "unspecified+no_connect"))
    )
    (net (code "89") (name "unconnected-(NAVDATA-Pad4)") (class "Default")
      (node (ref "NAVDATA") (pin "4") (pinfunction "4_4") (pintype "unspecified+no_connect"))
    )
    (net (code "90") (name "unconnected-(PASS_BRIEF-Pad1)") (class "Default")
      (node (ref "PASS_BRIEF") (pin "1") (pinfunction "1_1") (pintype "unspecified+no_connect"))
    )
    (net (code "91") (name "unconnected-(PASS_BRIEF-Pad4)") (class "Default")
      (node (ref "PASS_BRIEF") (pin "4") (pinfunction "4_4") (pintype "unspecified+no_connect"))
    )
    (net (code "92") (name "unconnected-(RADAR_MENU-Pad1)") (class "Default")
      (node (ref "RADAR_MENU") (pin "1") (pinfunction "1_1") (pintype "unspecified+no_connect"))
    )
    (net (code "93") (name "unconnected-(RADAR_MENU-Pad4)") (class "Default")
      (node (ref "RADAR_MENU") (pin "4") (pinfunction "4_4") (pintype "unspecified+no_connect"))
    )
    (net (code "94") (name "unconnected-(SYS-Pad1)") (class "Default")
      (node (ref "SYS") (pin "1") (pinfunction "1_1") (pintype "unspecified+no_connect"))
    )
    (net (code "95") (name "unconnected-(SYS-Pad4)") (class "Default")
      (node (ref "SYS") (pin "4") (pinfunction "4_4") (pintype "unspecified+no_connect"))
    )
    (net (code "96") (name "unconnected-(TERR_WX-Pad1)") (class "Default")
      (node (ref "TERR_WX") (pin "1") (pinfunction "1_1") (pintype "unspecified+no_connect"))
    )
    (net (code "97") (name "unconnected-(TERR_WX-Pad4)") (class "Default")
      (node (ref "TERR_WX") (pin "4") (pinfunction "4_4") (pintype "unspecified+no_connect"))
    )
    (net (code "98") (name "unconnected-(TFC-Pad1)") (class "Default")
      (node (ref "TFC") (pin "1") (pinfunction "1_1") (pintype "unspecified+no_connect"))
    )
    (net (code "99") (name "unconnected-(TFC-Pad4)") (class "Default")
      (node (ref "TFC") (pin "4") (pinfunction "4_4") (pintype "unspecified+no_connect"))
    )
    (net (code "100") (name "unconnected-(UPR_MENU-Pad1)") (class "Default")
      (node (ref "UPR_MENU") (pin "1") (pinfunction "1_1") (pintype "unspecified+no_connect"))
    )
    (net (code "101") (name "unconnected-(UPR_MENU-Pad4)") (class "Default")
      (node (ref "UPR_MENU") (pin "4") (pinfunction "4_4") (pintype "unspecified+no_connect"))
    )
    (net (code "102") (name "unconnected-(ZOOM_MINUS-Pad1)") (class "Default")
      (node (ref "ZOOM_MINUS") (pin "1") (pinfunction "1_1") (pintype "unspecified+no_connect"))
    )
    (net (code "103") (name "unconnected-(ZOOM_MINUS-Pad4)") (class "Default")
      (node (ref "ZOOM_MINUS") (pin "4") (pinfunction "4_4") (pintype "unspecified+no_connect"))
    )
    (net (code "104") (name "unconnected-(ZOOM_PLUS-Pad1)") (class "Default")
      (node (ref "ZOOM_PLUS") (pin "1") (pinfunction "1_1") (pintype "unspecified+no_connect"))
    )
    (net (code "105") (name "unconnected-(ZOOM_PLUS-Pad4)") (class "Default")
      (node (ref "ZOOM_PLUS") (pin "4") (pinfunction "4_4") (pintype "unspecified+no_connect"))
    )
  )
)
